# 20x20_adapter_tbs_v4_m2.net
KiCad netlist of a schematic drawn in EAGLE
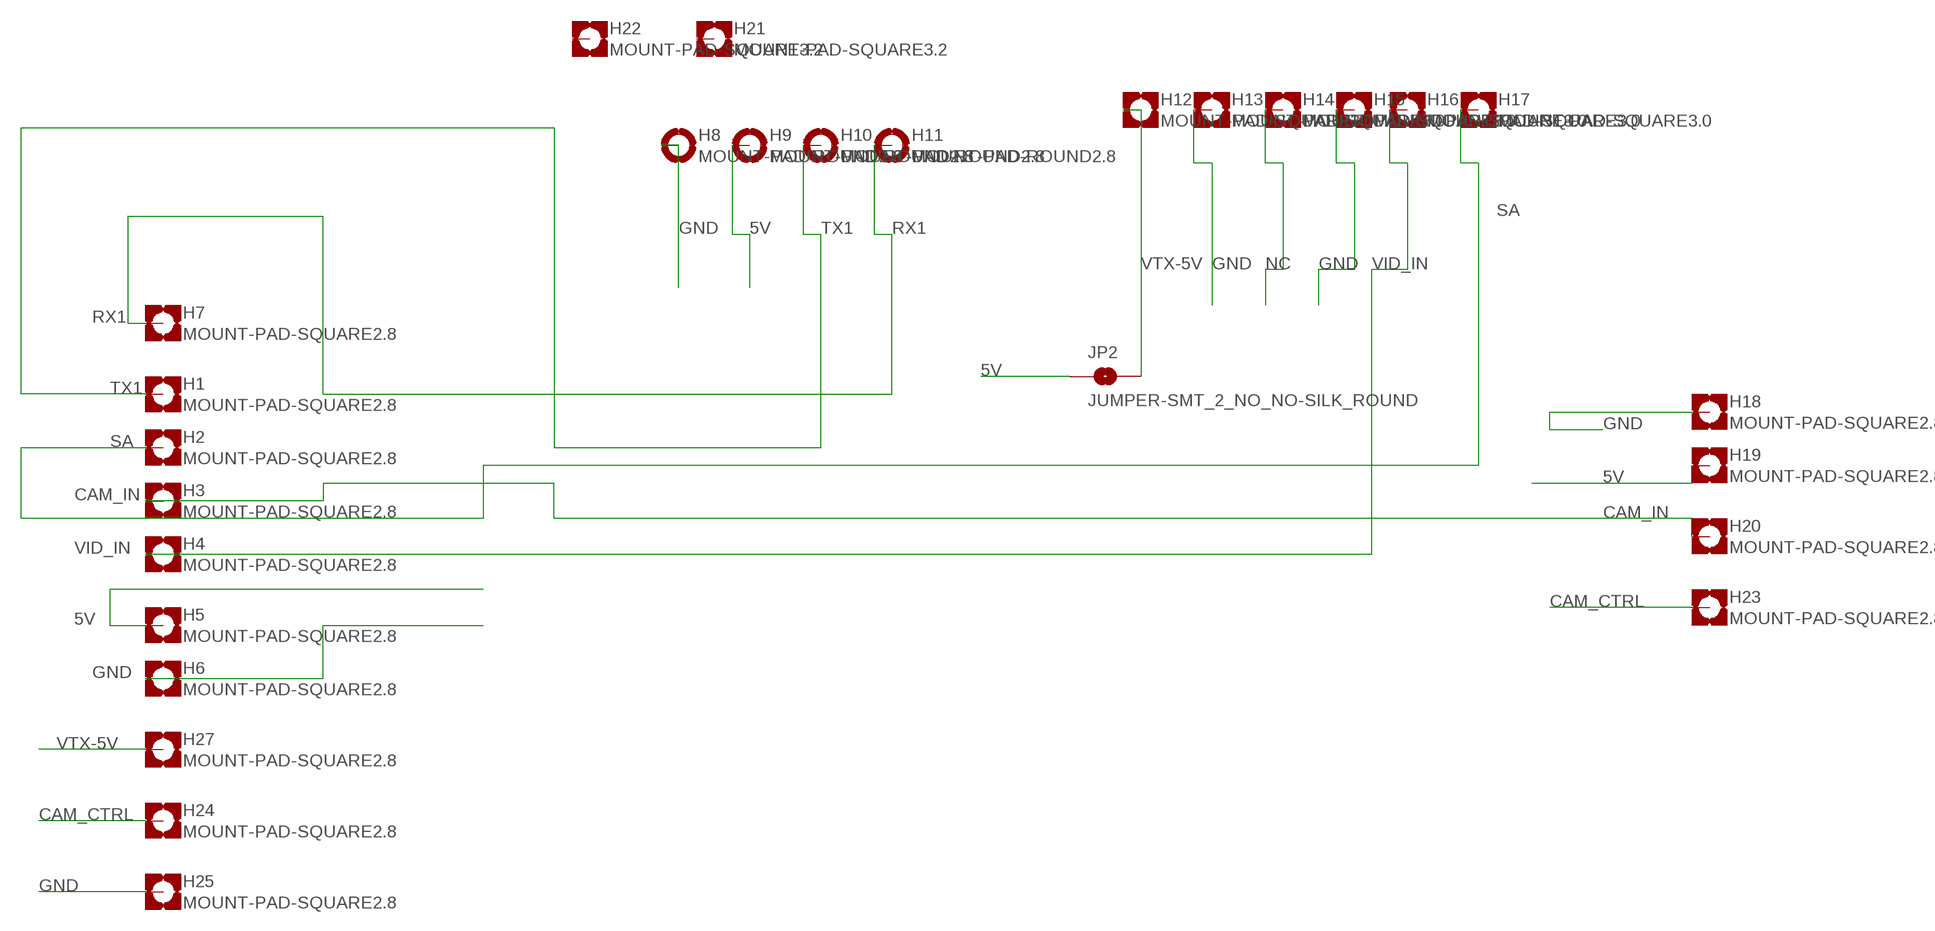
[diagram p0: schematic, sheet 1]

(export (version "E")
  (design (tool "Eeschema 10.0.6"))
  (components
    (comp (ref "H1")
      (value "MOUNT-PAD-SQUARE2.8")
      (footprint "eagle-import:2,8-PAD-SQUARE")
      (libsource (lib "eagle-import") (part "MOUNT-PAD-SQUARE2.8"))
    )
    (comp (ref "H2")
      (value "MOUNT-PAD-SQUARE2.8")
      (footprint "eagle-import:2,8-PAD-SQUARE")
      (libsource (lib "eagle-import") (part "MOUNT-PAD-SQUARE2.8"))
    )
    (comp (ref "H3")
      (value "MOUNT-PAD-SQUARE2.8")
      (footprint "eagle-import:2,8-PAD-SQUARE")
      (libsource (lib "eagle-import") (part "MOUNT-PAD-SQUARE2.8"))
    )
    (comp (ref "H4")
      (value "MOUNT-PAD-SQUARE2.8")
      (footprint "eagle-import:2,8-PAD-SQUARE")
      (libsource (lib "eagle-import") (part "MOUNT-PAD-SQUARE2.8"))
    )
    (comp (ref "H5")
      (value "MOUNT-PAD-SQUARE2.8")
      (footprint "eagle-import:2,8-PAD-SQUARE")
      (libsource (lib "eagle-import") (part "MOUNT-PAD-SQUARE2.8"))
    )
    (comp (ref "H6")
      (value "MOUNT-PAD-SQUARE2.8")
      (footprint "eagle-import:2,8-PAD-SQUARE")
      (libsource (lib "eagle-import") (part "MOUNT-PAD-SQUARE2.8"))
    )
    (comp (ref "H7")
      (value "MOUNT-PAD-SQUARE2.8")
      (footprint "eagle-import:2,8-PAD-SQUARE")
      (libsource (lib "eagle-import") (part "MOUNT-PAD-SQUARE2.8"))
    )
    (comp (ref "H8")
      (value "MOUNT-PAD-ROUND2.8")
      (footprint "eagle-import:1,0-PAD")
      (libsource (lib "eagle-import") (part "MOUNT-PAD-ROUND2.8"))
    )
    (comp (ref "H9")
      (value "MOUNT-PAD-ROUND2.8")
      (footprint "eagle-import:1,0-PAD")
      (libsource (lib "eagle-import") (part "MOUNT-PAD-ROUND2.8"))
    )
    (comp (ref "H10")
      (value "MOUNT-PAD-ROUND2.8")
      (footprint "eagle-import:1,0-PAD")
      (libsource (lib "eagle-import") (part "MOUNT-PAD-ROUND2.8"))
    )
    (comp (ref "H11")
      (value "MOUNT-PAD-ROUND2.8")
      (footprint "eagle-import:1,0-PAD")
      (libsource (lib "eagle-import") (part "MOUNT-PAD-ROUND2.8"))
    )
    (comp (ref "H12")
      (value "MOUNT-PAD-SQUARE3.0")
      (footprint "eagle-import:1,5-PAD-SQUARE")
      (libsource (lib "eagle-import") (part "MOUNT-PAD-SQUARE3.0"))
    )
    (comp (ref "H13")
      (value "MOUNT-PAD-SQUARE3.0")
      (footprint "eagle-import:1,5-PAD-SQUARE")
      (libsource (lib "eagle-import") (part "MOUNT-PAD-SQUARE3.0"))
    )
    (comp (ref "H14")
      (value "MOUNT-PAD-SQUARE3.0")
      (footprint "eagle-import:1,5-PAD-SQUARE")
      (libsource (lib "eagle-import") (part "MOUNT-PAD-SQUARE3.0"))
    )
    (comp (ref "H15")
      (value "MOUNT-PAD-SQUARE3.0")
      (footprint "eagle-import:1,5-PAD-SQUARE")
      (libsource (lib "eagle-import") (part "MOUNT-PAD-SQUARE3.0"))
    )
    (comp (ref "H16")
      (value "MOUNT-PAD-SQUARE3.0")
      (footprint "eagle-import:1,5-PAD-SQUARE")
      (libsource (lib "eagle-import") (part "MOUNT-PAD-SQUARE3.0"))
    )
    (comp (ref "H17")
      (value "MOUNT-PAD-SQUARE3.0")
      (footprint "eagle-import:1,5-PAD-SQUARE")
      (libsource (lib "eagle-import") (part "MOUNT-PAD-SQUARE3.0"))
    )
    (comp (ref "H18")
      (value "MOUNT-PAD-SQUARE2.8")
      (footprint "eagle-import:2,8-PAD-SQUARE")
      (libsource (lib "eagle-import") (part "MOUNT-PAD-SQUARE2.8"))
    )
    (comp (ref "H19")
      (value "MOUNT-PAD-SQUARE2.8")
      (footprint "eagle-import:2,8-PAD-SQUARE")
      (libsource (lib "eagle-import") (part "MOUNT-PAD-SQUARE2.8"))
    )
    (comp (ref "H20")
      (value "MOUNT-PAD-SQUARE2.8")
      (footprint "eagle-import:2,8-PAD-SQUARE")
      (libsource (lib "eagle-import") (part "MOUNT-PAD-SQUARE2.8"))
    )
    (comp (ref "H21")
      (value "MOUNT-PAD-SQUARE3.2")
      (footprint "eagle-import:3,2-PAD-SQUARE")
      (libsource (lib "eagle-import") (part "MOUNT-PAD-SQUARE3.2"))
    )
    (comp (ref "H22")
      (value "MOUNT-PAD-SQUARE3.2")
      (footprint "eagle-import:3,2-PAD-SQUARE")
      (libsource (lib "eagle-import") (part "MOUNT-PAD-SQUARE3.2"))
    )
    (comp (ref "H23")
      (value "MOUNT-PAD-SQUARE2.8")
      (footprint "eagle-import:2,8-PAD-SQUARE")
      (libsource (lib "eagle-import") (part "MOUNT-PAD-SQUARE2.8"))
    )
    (comp (ref "H24")
      (value "MOUNT-PAD-SQUARE2.8")
      (footprint "eagle-import:2,8-PAD-SQUARE")
      (libsource (lib "eagle-import") (part "MOUNT-PAD-SQUARE2.8"))
    )
    (comp (ref "H25")
      (value "MOUNT-PAD-SQUARE2.8")
      (footprint "eagle-import:2,8-PAD-SQUARE")
      (libsource (lib "eagle-import") (part "MOUNT-PAD-SQUARE2.8"))
    )
    (comp (ref "H27")
      (value "MOUNT-PAD-SQUARE2.8")
      (footprint "eagle-import:2,8-PAD-SQUARE")
      (libsource (lib "eagle-import") (part "MOUNT-PAD-SQUARE2.8"))
    )
    (comp (ref "JP2")
      (value "JUMPER-SMT_2_NO_NO-SILK_ROUND")
      (footprint "eagle-import:SMT-JUMPER_2_NO_NO-SILK_ROUND")
      (libsource (lib "eagle-import") (part "JUMPER-SMT_2_NO_NO-SILK_ROUND"))
    )
  )
  (nets
    (net (code "1") (name "/5V") (class "Default")
      (node (ref "H19") (pin "P$2") (pinfunction "MOUNT_P$2") (pintype "passive"))
      (node (ref "H5") (pin "P$2") (pinfunction "MOUNT_P$2") (pintype "passive"))
      (node (ref "H9") (pin "B1,0") (pinfunction "MOUNT_B1,0") (pintype "passive"))
      (node (ref "JP2") (pin "1") (pinfunction "1_1") (pintype "passive"))
    )
    (net (code "2") (name "/CAM_CTRL") (class "Default")
      (node (ref "H23") (pin "P$2") (pinfunction "MOUNT_P$2") (pintype "passive"))
      (node (ref "H24") (pin "P$2") (pinfunction "MOUNT_P$2") (pintype "passive"))
    )
    (net (code "3") (name "/CAM_IN") (class "Default")
      (node (ref "H20") (pin "P$2") (pinfunction "MOUNT_P$2") (pintype "passive"))
      (node (ref "H3") (pin "P$2") (pinfunction "MOUNT_P$2") (pintype "passive"))
    )
    (net (code "4") (name "/GND") (class "Default")
      (node (ref "H13") (pin "P$1") (pinfunction "MOUNT_P$1") (pintype "passive"))
      (node (ref "H15") (pin "P$1") (pinfunction "MOUNT_P$1") (pintype "passive"))
      (node (ref "H18") (pin "P$2") (pinfunction "MOUNT_P$2") (pintype "passive"))
      (node (ref "H25") (pin "P$2") (pinfunction "MOUNT_P$2") (pintype "passive"))
      (node (ref "H6") (pin "P$2") (pinfunction "MOUNT_P$2") (pintype "passive"))
      (node (ref "H8") (pin "B1,0") (pinfunction "MOUNT_B1,0") (pintype "passive"))
    )
    (net (code "5") (name "/NC") (class "Default")
      (node (ref "H14") (pin "P$1") (pinfunction "MOUNT_P$1") (pintype "passive"))
    )
    (net (code "6") (name "/RX1") (class "Default")
      (node (ref "H11") (pin "B1,0") (pinfunction "MOUNT_B1,0") (pintype "passive"))
      (node (ref "H7") (pin "P$2") (pinfunction "MOUNT_P$2") (pintype "passive"))
    )
    (net (code "7") (name "/SA") (class "Default")
      (node (ref "H17") (pin "P$1") (pinfunction "MOUNT_P$1") (pintype "passive"))
      (node (ref "H2") (pin "P$2") (pinfunction "MOUNT_P$2") (pintype "passive"))
    )
    (net (code "8") (name "/TX1") (class "Default")
      (node (ref "H1") (pin "P$2") (pinfunction "MOUNT_P$2") (pintype "passive"))
      (node (ref "H10") (pin "B1,0") (pinfunction "MOUNT_B1,0") (pintype "passive"))
    )
    (net (code "9") (name "/VID_IN") (class "Default")
      (node (ref "H16") (pin "P$1") (pinfunction "MOUNT_P$1") (pintype "passive"))
      (node (ref "H4") (pin "P$2") (pinfunction "MOUNT_P$2") (pintype "passive"))
    )
    (net (code "10") (name "/VTX-5V") (class "Default")
      (node (ref "H12") (pin "P$1") (pinfunction "MOUNT_P$1") (pintype "passive"))
      (node (ref "H27") (pin "P$2") (pinfunction "MOUNT_P$2") (pintype "passive"))
      (node (ref "JP2") (pin "2") (pinfunction "2_2") (pintype "passive"))
    )
    (net (code "11") (name "unconnected-(H21-MOUNT-PadP$1)") (class "Default")
      (node (ref "H21") (pin "P$1") (pinfunction "MOUNT_P$1") (pintype "passive"))
    )
    (net (code "12") (name "unconnected-(H22-MOUNT-PadP$1)") (class "Default")
      (node (ref "H22") (pin "P$1") (pinfunction "MOUNT_P$1") (pintype "passive"))
    )
  )
)
